# Logic.net
KiCad netlist of a schematic drawn in Altium Designer
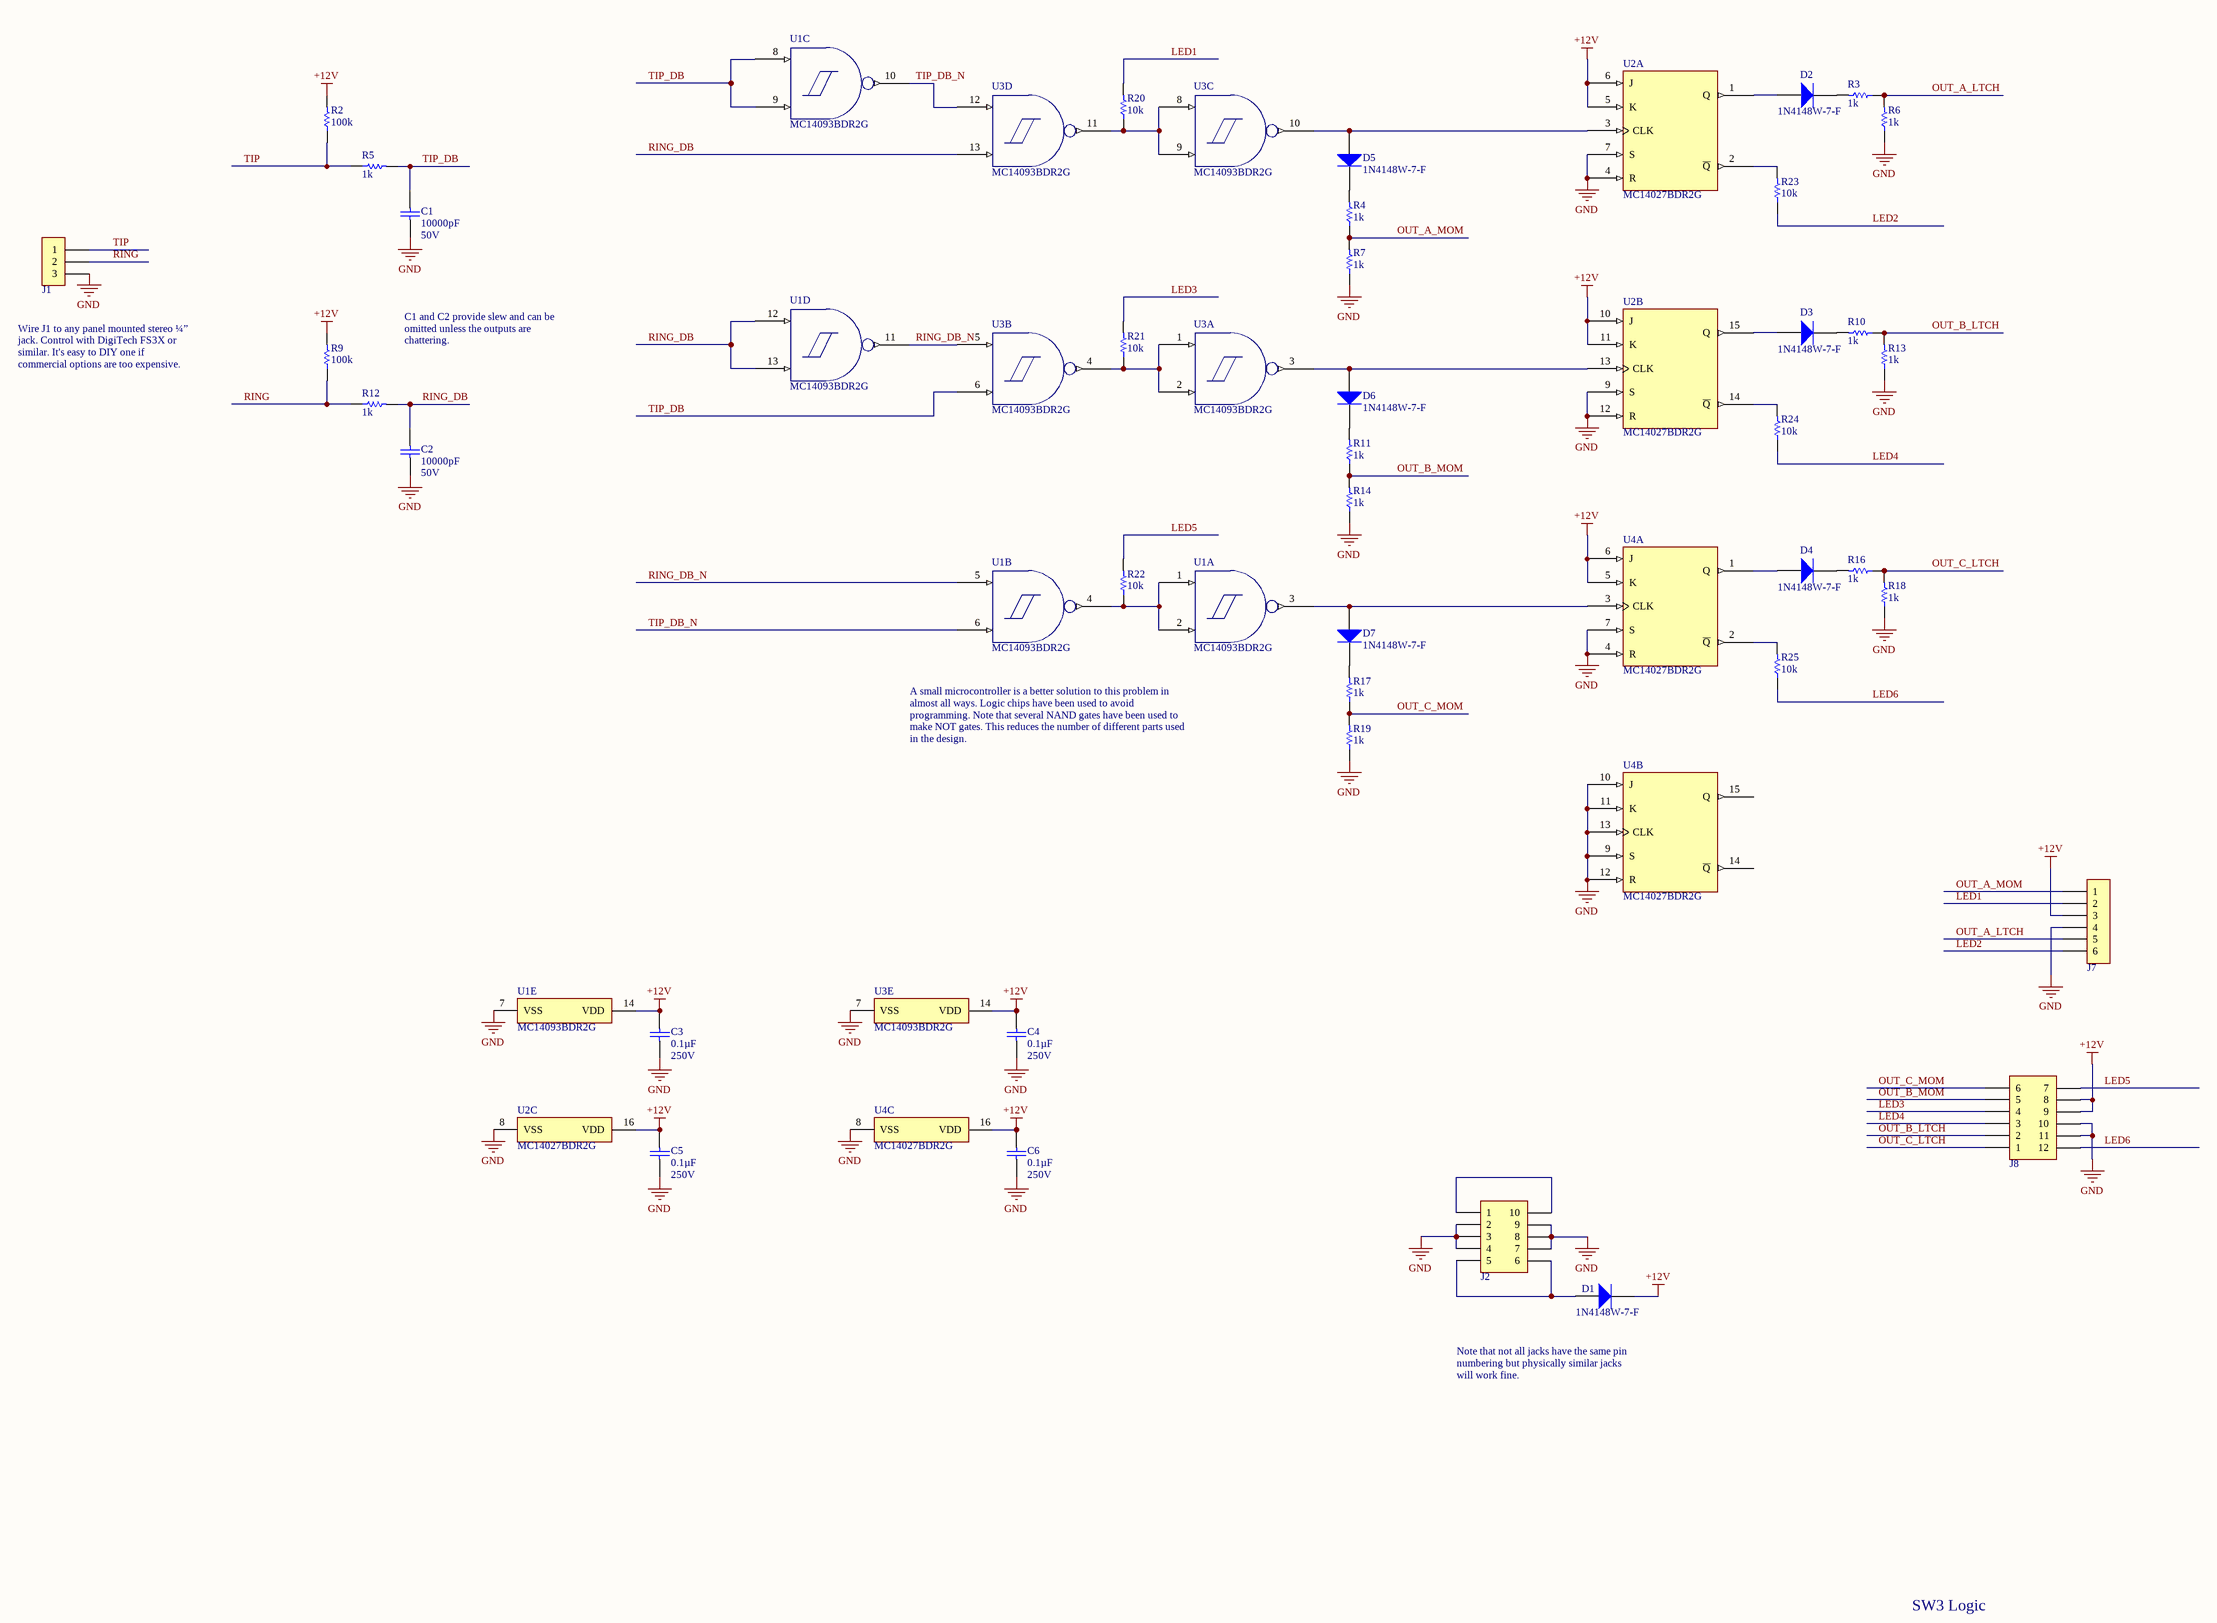
[diagram p0: Logic.SchDoc]

(export (version "E")
  (design (tool "Eeschema 10.0.6"))
  (components
    (comp (ref "C1")
      (value "10000pF")
      (footprint "Chip0805")
      (description "CAP CER 10000PF 50V 5% NP0 0805")
      (fields
        (field (name "VOLTAGE") "50V")
        (field (name "PARTNUMBER") "C2012C0G1H103J060AA")
        (field (name "MANUFACTURER") "TDK Corporation")
      )
      (libsource (lib "Passives") (part "CAP"))
    )
    (comp (ref "C2")
      (value "10000pF")
      (footprint "Chip0805")
      (description "CAP CER 10000PF 50V 5% NP0 0805")
      (fields
        (field (name "VOLTAGE") "50V")
        (field (name "PARTNUMBER") "C2012C0G1H103J060AA")
        (field (name "MANUFACTURER") "TDK Corporation")
      )
      (libsource (lib "Passives") (part "CAP"))
    )
    (comp (ref "C3")
      (value "0.1µF")
      (footprint "Chip0805")
      (description "CAP CER 0.1UF 250V 10% X7T 0805")
      (fields
        (field (name "VOLTAGE") "250V")
        (field (name "PARTNUMBER") "C2012X7T2E104K125AA")
        (field (name "MANUFACTURER") "TDK Corporation")
      )
      (libsource (lib "Passives") (part "CAP"))
    )
    (comp (ref "C4")
      (value "0.1µF")
      (footprint "Chip0805")
      (description "CAP CER 0.1UF 250V 10% X7T 0805")
      (fields
        (field (name "VOLTAGE") "250V")
        (field (name "PARTNUMBER") "C2012X7T2E104K125AA")
        (field (name "MANUFACTURER") "TDK Corporation")
      )
      (libsource (lib "Passives") (part "CAP"))
    )
    (comp (ref "C5")
      (value "0.1µF")
      (footprint "Chip0805")
      (description "CAP CER 0.1UF 250V 10% X7T 0805")
      (fields
        (field (name "VOLTAGE") "250V")
        (field (name "PARTNUMBER") "C2012X7T2E104K125AA")
        (field (name "MANUFACTURER") "TDK Corporation")
      )
      (libsource (lib "Passives") (part "CAP"))
    )
    (comp (ref "C6")
      (value "0.1µF")
      (footprint "Chip0805")
      (description "CAP CER 0.1UF 250V 10% X7T 0805")
      (fields
        (field (name "VOLTAGE") "250V")
        (field (name "PARTNUMBER") "C2012X7T2E104K125AA")
        (field (name "MANUFACTURER") "TDK Corporation")
      )
      (libsource (lib "Passives") (part "CAP"))
    )
    (comp (ref "D1")
      (value "1N4148W-7-F")
      (footprint "SOD-123")
      (description "DIODE SWITCH 100V 0.15A SOD123")
      (fields (field (name "MANUFACTURER") "Diodes Incorporated"))
      (libsource (lib "Semiconductor") (part "DIODE"))
    )
    (comp (ref "D2")
      (value "1N4148W-7-F")
      (footprint "SOD-123")
      (description "DIODE SWITCH 100V 0.15A SOD123")
      (fields (field (name "MANUFACTURER") "Diodes Incorporated"))
      (libsource (lib "Semiconductor") (part "DIODE"))
    )
    (comp (ref "D3")
      (value "1N4148W-7-F")
      (footprint "SOD-123")
      (description "DIODE SWITCH 100V 0.15A SOD123")
      (fields (field (name "MANUFACTURER") "Diodes Incorporated"))
      (libsource (lib "Semiconductor") (part "DIODE"))
    )
    (comp (ref "D4")
      (value "1N4148W-7-F")
      (footprint "SOD-123")
      (description "DIODE SWITCH 100V 0.15A SOD123")
      (fields (field (name "MANUFACTURER") "Diodes Incorporated"))
      (libsource (lib "Semiconductor") (part "DIODE"))
    )
    (comp (ref "D5")
      (value "1N4148W-7-F")
      (footprint "SOD-123")
      (description "DIODE SWITCH 100V 0.15A SOD123")
      (fields (field (name "MANUFACTURER") "Diodes Incorporated"))
      (libsource (lib "Semiconductor") (part "DIODE"))
    )
    (comp (ref "D6")
      (value "1N4148W-7-F")
      (footprint "SOD-123")
      (description "DIODE SWITCH 100V 0.15A SOD123")
      (fields (field (name "MANUFACTURER") "Diodes Incorporated"))
      (libsource (lib "Semiconductor") (part "DIODE"))
    )
    (comp (ref "D7")
      (value "1N4148W-7-F")
      (footprint "SOD-123")
      (description "DIODE SWITCH 100V 0.15A SOD123")
      (fields (field (name "MANUFACTURER") "Diodes Incorporated"))
      (libsource (lib "Semiconductor") (part "DIODE"))
    )
    (comp (ref "J1")
      (value "3-644456-3")
      (footprint "TE_3-644456-3")
      (description "CONN HEADER VERT 3POS .100 TIN")
      (fields (field (name "MANUFACTURER") "TE Connectivity"))
      (libsource (lib "Connectors") (part "HEADER_1x3"))
    )
    (comp (ref "J2")
      (value "75869-101LF")
      (footprint "IDC_100_2x5")
      (description "CONN HEADER 10POS DUAL VERT PCB")
      (fields (field (name "MANUFACTURER") "FCI"))
      (libsource (lib "Connectors") (part "HEADER_2x5"))
    )
    (comp (ref "J7")
      (value "535584-1")
      (footprint "TE_535584-1")
      (description "CONN RECEPT 6POS .100 VERT")
      (fields (field (name "MANUFACTURER") "TE Connectivity AMP Connectors"))
      (libsource (lib "Connectors") (part "HEADER_1x6"))
    )
    (comp (ref "J8")
      (value "5-534998-6")
      (footprint "TE_5-534998-6")
      (description "CONN RECEPT 12POS .100 VERT DUAL")
      (fields (field (name "MANUFACTURER") "TE Connectivity AMP Connectors"))
      (libsource (lib "Connectors") (part "HEADER_2x6"))
    )
    (comp (ref "R2")
      (value "100k")
      (footprint "Chip0805")
      (description "RES 100K OHM 1/8W 1% 0805 SMD")
      (fields (field (name "PARTNUMBER") "CRCW0805100KFKEA") (field (name "MANUFACTURER") "Vishay Dale"))
      (libsource (lib "Passives") (part "RES"))
    )
    (comp (ref "R3")
      (value "1k")
      (footprint "Chip0805")
      (description "RES 1.00K OHM 1/8W 1% 0805 SMD")
      (fields (field (name "PARTNUMBER") "CRCW08051K00FKEA") (field (name "MANUFACTURER") "Vishay Dale"))
      (libsource (lib "Passives") (part "RES"))
    )
    (comp (ref "R4")
      (value "1k")
      (footprint "Chip0805")
      (description "RES 1.00K OHM 1/8W 1% 0805 SMD")
      (fields (field (name "PARTNUMBER") "CRCW08051K00FKEA") (field (name "MANUFACTURER") "Vishay Dale"))
      (libsource (lib "Passives") (part "RES"))
    )
    (comp (ref "R5")
      (value "1k")
      (footprint "Chip0805")
      (description "RES 1.00K OHM 1/8W 1% 0805 SMD")
      (fields (field (name "PARTNUMBER") "CRCW08051K00FKEA") (field (name "MANUFACTURER") "Vishay Dale"))
      (libsource (lib "Passives") (part "RES"))
    )
    (comp (ref "R6")
      (value "1k")
      (footprint "Chip0805")
      (description "RES 1.00K OHM 1/8W 1% 0805 SMD")
      (fields (field (name "PARTNUMBER") "CRCW08051K00FKEA") (field (name "MANUFACTURER") "Vishay Dale"))
      (libsource (lib "Passives") (part "RES"))
    )
    (comp (ref "R7")
      (value "1k")
      (footprint "Chip0805")
      (description "RES 1.00K OHM 1/8W 1% 0805 SMD")
      (fields (field (name "PARTNUMBER") "CRCW08051K00FKEA") (field (name "MANUFACTURER") "Vishay Dale"))
      (libsource (lib "Passives") (part "RES"))
    )
    (comp (ref "R9")
      (value "100k")
      (footprint "Chip0805")
      (description "RES 100K OHM 1/8W 1% 0805 SMD")
      (fields (field (name "PARTNUMBER") "CRCW0805100KFKEA") (field (name "MANUFACTURER") "Vishay Dale"))
      (libsource (lib "Passives") (part "RES"))
    )
    (comp (ref "R10")
      (value "1k")
      (footprint "Chip0805")
      (description "RES 1.00K OHM 1/8W 1% 0805 SMD")
      (fields (field (name "PARTNUMBER") "CRCW08051K00FKEA") (field (name "MANUFACTURER") "Vishay Dale"))
      (libsource (lib "Passives") (part "RES"))
    )
    (comp (ref "R11")
      (value "1k")
      (footprint "Chip0805")
      (description "RES 1.00K OHM 1/8W 1% 0805 SMD")
      (fields (field (name "PARTNUMBER") "CRCW08051K00FKEA") (field (name "MANUFACTURER") "Vishay Dale"))
      (libsource (lib "Passives") (part "RES"))
    )
    (comp (ref "R12")
      (value "1k")
      (footprint "Chip0805")
      (description "RES 1.00K OHM 1/8W 1% 0805 SMD")
      (fields (field (name "PARTNUMBER") "CRCW08051K00FKEA") (field (name "MANUFACTURER") "Vishay Dale"))
      (libsource (lib "Passives") (part "RES"))
    )
    (comp (ref "R13")
      (value "1k")
      (footprint "Chip0805")
      (description "RES 1.00K OHM 1/8W 1% 0805 SMD")
      (fields (field (name "PARTNUMBER") "CRCW08051K00FKEA") (field (name "MANUFACTURER") "Vishay Dale"))
      (libsource (lib "Passives") (part "RES"))
    )
    (comp (ref "R14")
      (value "1k")
      (footprint "Chip0805")
      (description "RES 1.00K OHM 1/8W 1% 0805 SMD")
      (fields (field (name "PARTNUMBER") "CRCW08051K00FKEA") (field (name "MANUFACTURER") "Vishay Dale"))
      (libsource (lib "Passives") (part "RES"))
    )
    (comp (ref "R16")
      (value "1k")
      (footprint "Chip0805")
      (description "RES 1.00K OHM 1/8W 1% 0805 SMD")
      (fields (field (name "PARTNUMBER") "CRCW08051K00FKEA") (field (name "MANUFACTURER") "Vishay Dale"))
      (libsource (lib "Passives") (part "RES"))
    )
    (comp (ref "R17")
      (value "1k")
      (footprint "Chip0805")
      (description "RES 1.00K OHM 1/8W 1% 0805 SMD")
      (fields (field (name "PARTNUMBER") "CRCW08051K00FKEA") (field (name "MANUFACTURER") "Vishay Dale"))
      (libsource (lib "Passives") (part "RES"))
    )
    (comp (ref "R18")
      (value "1k")
      (footprint "Chip0805")
      (description "RES 1.00K OHM 1/8W 1% 0805 SMD")
      (fields (field (name "PARTNUMBER") "CRCW08051K00FKEA") (field (name "MANUFACTURER") "Vishay Dale"))
      (libsource (lib "Passives") (part "RES"))
    )
    (comp (ref "R19")
      (value "1k")
      (footprint "Chip0805")
      (description "RES 1.00K OHM 1/8W 1% 0805 SMD")
      (fields (field (name "PARTNUMBER") "CRCW08051K00FKEA") (field (name "MANUFACTURER") "Vishay Dale"))
      (libsource (lib "Passives") (part "RES"))
    )
    (comp (ref "R20")
      (value "10k")
      (footprint "Chip0805")
      (description "RES 10.0K OHM 1/8W 1% 0805 SMD")
      (fields (field (name "PARTNUMBER") "CRCW080510K0FKEA") (field (name "MANUFACTURER") "Vishay Dale"))
      (libsource (lib "Passives") (part "RES"))
    )
    (comp (ref "R21")
      (value "10k")
      (footprint "Chip0805")
      (description "RES 10.0K OHM 1/8W 1% 0805 SMD")
      (fields (field (name "PARTNUMBER") "CRCW080510K0FKEA") (field (name "MANUFACTURER") "Vishay Dale"))
      (libsource (lib "Passives") (part "RES"))
    )
    (comp (ref "R22")
      (value "10k")
      (footprint "Chip0805")
      (description "RES 10.0K OHM 1/8W 1% 0805 SMD")
      (fields (field (name "PARTNUMBER") "CRCW080510K0FKEA") (field (name "MANUFACTURER") "Vishay Dale"))
      (libsource (lib "Passives") (part "RES"))
    )
    (comp (ref "R23")
      (value "10k")
      (footprint "Chip0805")
      (description "RES 10.0K OHM 1/8W 1% 0805 SMD")
      (fields (field (name "PARTNUMBER") "CRCW080510K0FKEA") (field (name "MANUFACTURER") "Vishay Dale"))
      (libsource (lib "Passives") (part "RES"))
    )
    (comp (ref "R24")
      (value "10k")
      (footprint "Chip0805")
      (description "RES 10.0K OHM 1/8W 1% 0805 SMD")
      (fields (field (name "PARTNUMBER") "CRCW080510K0FKEA") (field (name "MANUFACTURER") "Vishay Dale"))
      (libsource (lib "Passives") (part "RES"))
    )
    (comp (ref "R25")
      (value "10k")
      (footprint "Chip0805")
      (description "RES 10.0K OHM 1/8W 1% 0805 SMD")
      (fields (field (name "PARTNUMBER") "CRCW080510K0FKEA") (field (name "MANUFACTURER") "Vishay Dale"))
      (libsource (lib "Passives") (part "RES"))
    )
    (comp (ref "U1")
      (value "MC14093BDR2G")
      (footprint "14-SOIC")
      (description "IC GATE NAND 4CH 2-INP 14SOIC")
      (fields (field (name "MANUFACTURER") "onsemi"))
      (libsource (lib "ICs") (part "Quad_Schmitt_NAND"))
    )
    (comp (ref "U2")
      (value "MC14027BDR2G")
      (footprint "16-SOIC")
      (description "IC FF JK TYPE DUAL 1BIT 16SOIC")
      (fields (field (name "MANUFACTURER") "onsemi"))
      (libsource (lib "ICs") (part "Dual_JK_FF"))
    )
    (comp (ref "U3")
      (value "MC14093BDR2G")
      (footprint "14-SOIC")
      (description "IC GATE NAND 4CH 2-INP 14SOIC")
      (fields (field (name "MANUFACTURER") "onsemi"))
      (libsource (lib "ICs") (part "Quad_Schmitt_NAND"))
    )
    (comp (ref "U4")
      (value "MC14027BDR2G")
      (footprint "16-SOIC")
      (description "IC FF JK TYPE DUAL 1BIT 16SOIC")
      (fields (field (name "MANUFACTURER") "onsemi"))
      (libsource (lib "ICs") (part "Dual_JK_FF"))
    )
  )
  (nets
    (net (code "1") (name "+12V") (class "Default")
      (node (ref "C3") (pin "2") (pinfunction "2_2") (pintype "passive"))
      (node (ref "C4") (pin "2") (pinfunction "2_2") (pintype "passive"))
      (node (ref "C5") (pin "2") (pinfunction "2_2") (pintype "passive"))
      (node (ref "C6") (pin "2") (pinfunction "2_2") (pintype "passive"))
      (node (ref "D1") (pin "1") (pinfunction "C_1") (pintype "passive"))
      (node (ref "J7") (pin "3") (pinfunction "3_3") (pintype "passive"))
      (node (ref "J8") (pin "8") (pinfunction "8_8") (pintype "passive"))
      (node (ref "J8") (pin "9") (pinfunction "9_9") (pintype "passive"))
      (node (ref "R2") (pin "2") (pinfunction "2_2") (pintype "passive"))
      (node (ref "R9") (pin "2") (pinfunction "2_2") (pintype "passive"))
      (node (ref "U1") (pin "14") (pinfunction "VDD_14") (pintype "passive"))
      (node (ref "U2") (pin "10") (pinfunction "J_10") (pintype "input"))
      (node (ref "U2") (pin "11") (pinfunction "K_11") (pintype "input"))
      (node (ref "U2") (pin "16") (pinfunction "VDD_16") (pintype "passive"))
      (node (ref "U2") (pin "5") (pinfunction "K_5") (pintype "input"))
      (node (ref "U2") (pin "6") (pinfunction "J_6") (pintype "input"))
      (node (ref "U3") (pin "14") (pinfunction "VDD_14") (pintype "passive"))
      (node (ref "U4") (pin "16") (pinfunction "VDD_16") (pintype "passive"))
      (node (ref "U4") (pin "5") (pinfunction "K_5") (pintype "input"))
      (node (ref "U4") (pin "6") (pinfunction "J_6") (pintype "input"))
    )
    (net (code "2") (name "/LED1") (class "Default")
      (node (ref "J7") (pin "2") (pinfunction "2_2") (pintype "passive"))
      (node (ref "R20") (pin "2") (pinfunction "2_2") (pintype "passive"))
    )
    (net (code "3") (name "/LED2") (class "Default")
      (node (ref "J7") (pin "6") (pinfunction "6_6") (pintype "passive"))
      (node (ref "R23") (pin "1") (pinfunction "1_1") (pintype "passive"))
    )
    (net (code "4") (name "/LED3") (class "Default")
      (node (ref "J8") (pin "4") (pinfunction "4_4") (pintype "passive"))
      (node (ref "R21") (pin "2") (pinfunction "2_2") (pintype "passive"))
    )
    (net (code "5") (name "/LED4") (class "Default")
      (node (ref "J8") (pin "3") (pinfunction "3_3") (pintype "passive"))
      (node (ref "R24") (pin "1") (pinfunction "1_1") (pintype "passive"))
    )
    (net (code "6") (name "/LED5") (class "Default")
      (node (ref "J8") (pin "7") (pinfunction "7_7") (pintype "passive"))
      (node (ref "R22") (pin "2") (pinfunction "2_2") (pintype "passive"))
    )
    (net (code "7") (name "/LED6") (class "Default")
      (node (ref "J8") (pin "12") (pinfunction "12_12") (pintype "passive"))
      (node (ref "R25") (pin "1") (pinfunction "1_1") (pintype "passive"))
    )
    (net (code "8") (name "/OUT_A_LTCH") (class "Default")
      (node (ref "J7") (pin "5") (pinfunction "5_5") (pintype "passive"))
      (node (ref "R3") (pin "1") (pinfunction "1_1") (pintype "passive"))
      (node (ref "R6") (pin "2") (pinfunction "2_2") (pintype "passive"))
    )
    (net (code "9") (name "/OUT_A_MOM") (class "Default")
      (node (ref "J7") (pin "1") (pinfunction "1_1") (pintype "passive"))
      (node (ref "R4") (pin "1") (pinfunction "1_1") (pintype "passive"))
      (node (ref "R7") (pin "2") (pinfunction "2_2") (pintype "passive"))
    )
    (net (code "10") (name "/OUT_B_LTCH") (class "Default")
      (node (ref "J8") (pin "2") (pinfunction "2_2") (pintype "passive"))
      (node (ref "R10") (pin "1") (pinfunction "1_1") (pintype "passive"))
      (node (ref "R13") (pin "2") (pinfunction "2_2") (pintype "passive"))
    )
    (net (code "11") (name "/OUT_B_MOM") (class "Default")
      (node (ref "J8") (pin "5") (pinfunction "5_5") (pintype "passive"))
      (node (ref "R11") (pin "1") (pinfunction "1_1") (pintype "passive"))
      (node (ref "R14") (pin "2") (pinfunction "2_2") (pintype "passive"))
    )
    (net (code "12") (name "/OUT_C_LTCH") (class "Default")
      (node (ref "J8") (pin "1") (pinfunction "1_1") (pintype "passive"))
      (node (ref "R16") (pin "1") (pinfunction "1_1") (pintype "passive"))
      (node (ref "R18") (pin "2") (pinfunction "2_2") (pintype "passive"))
    )
    (net (code "13") (name "/OUT_C_MOM") (class "Default")
      (node (ref "J8") (pin "6") (pinfunction "6_6") (pintype "passive"))
      (node (ref "R17") (pin "1") (pinfunction "1_1") (pintype "passive"))
      (node (ref "R19") (pin "2") (pinfunction "2_2") (pintype "passive"))
    )
    (net (code "14") (name "/RING") (class "Default")
      (node (ref "J1") (pin "2") (pinfunction "2_2") (pintype "passive"))
      (node (ref "R12") (pin "1") (pinfunction "1_1") (pintype "passive"))
      (node (ref "R9") (pin "1") (pinfunction "1_1") (pintype "passive"))
    )
    (net (code "15") (name "/RING_DB") (class "Default")
      (node (ref "C2") (pin "2") (pinfunction "2_2") (pintype "passive"))
      (node (ref "R12") (pin "2") (pinfunction "2_2") (pintype "passive"))
      (node (ref "U1") (pin "12") (pinfunction "12_12") (pintype "input"))
      (node (ref "U1") (pin "13") (pinfunction "13_13") (pintype "input"))
      (node (ref "U3") (pin "13") (pinfunction "13_13") (pintype "input"))
    )
    (net (code "16") (name "/RING_DB_N") (class "Default")
      (node (ref "U1") (pin "11") (pinfunction "11_11") (pintype "output"))
      (node (ref "U1") (pin "5") (pinfunction "5_5") (pintype "input"))
      (node (ref "U3") (pin "5") (pinfunction "5_5") (pintype "input"))
    )
    (net (code "17") (name "/TIP") (class "Default")
      (node (ref "J1") (pin "1") (pinfunction "1_1") (pintype "passive"))
      (node (ref "R2") (pin "1") (pinfunction "1_1") (pintype "passive"))
      (node (ref "R5") (pin "1") (pinfunction "1_1") (pintype "passive"))
    )
    (net (code "18") (name "/TIP_DB") (class "Default")
      (node (ref "C1") (pin "2") (pinfunction "2_2") (pintype "passive"))
      (node (ref "R5") (pin "2") (pinfunction "2_2") (pintype "passive"))
      (node (ref "U1") (pin "8") (pinfunction "8_8") (pintype "input"))
      (node (ref "U1") (pin "9") (pinfunction "9_9") (pintype "input"))
      (node (ref "U3") (pin "6") (pinfunction "6_6") (pintype "input"))
    )
    (net (code "19") (name "/TIP_DB_N") (class "Default")
      (node (ref "U1") (pin "10") (pinfunction "10_10") (pintype "output"))
      (node (ref "U1") (pin "6") (pinfunction "6_6") (pintype "input"))
      (node (ref "U3") (pin "12") (pinfunction "12_12") (pintype "input"))
    )
    (net (code "20") (name "GND") (class "Default")
      (node (ref "C1") (pin "1") (pinfunction "1_1") (pintype "passive"))
      (node (ref "C2") (pin "1") (pinfunction "1_1") (pintype "passive"))
      (node (ref "C3") (pin "1") (pinfunction "1_1") (pintype "passive"))
      (node (ref "C4") (pin "1") (pinfunction "1_1") (pintype "passive"))
      (node (ref "C5") (pin "1") (pinfunction "1_1") (pintype "passive"))
      (node (ref "C6") (pin "1") (pinfunction "1_1") (pintype "passive"))
      (node (ref "J1") (pin "3") (pinfunction "3_3") (pintype "passive"))
      (node (ref "J2") (pin "2") (pinfunction "2_2") (pintype "passive"))
      (node (ref "J2") (pin "3") (pinfunction "3_3") (pintype "passive"))
      (node (ref "J2") (pin "4") (pinfunction "4_4") (pintype "passive"))
      (node (ref "J2") (pin "7") (pinfunction "7_7") (pintype "passive"))
      (node (ref "J2") (pin "8") (pinfunction "8_8") (pintype "passive"))
      (node (ref "J2") (pin "9") (pinfunction "9_9") (pintype "passive"))
      (node (ref "J7") (pin "4") (pinfunction "4_4") (pintype "passive"))
      (node (ref "J8") (pin "10") (pinfunction "10_10") (pintype "passive"))
      (node (ref "J8") (pin "11") (pinfunction "11_11") (pintype "passive"))
      (node (ref "R13") (pin "1") (pinfunction "1_1") (pintype "passive"))
      (node (ref "R14") (pin "1") (pinfunction "1_1") (pintype "passive"))
      (node (ref "R18") (pin "1") (pinfunction "1_1") (pintype "passive"))
      (node (ref "R19") (pin "1") (pinfunction "1_1") (pintype "passive"))
      (node (ref "R6") (pin "1") (pinfunction "1_1") (pintype "passive"))
      (node (ref "R7") (pin "1") (pinfunction "1_1") (pintype "passive"))
      (node (ref "U1") (pin "7") (pinfunction "VSS_7") (pintype "passive"))
      (node (ref "U2") (pin "12") (pinfunction "R_12") (pintype "input"))
      (node (ref "U2") (pin "4") (pinfunction "R_4") (pintype "input"))
      (node (ref "U2") (pin "7") (pinfunction "S_7") (pintype "input"))
      (node (ref "U2") (pin "8") (pinfunction "VSS_8") (pintype "passive"))
      (node (ref "U2") (pin "9") (pinfunction "S_9") (pintype "input"))
      (node (ref "U3") (pin "7") (pinfunction "VSS_7") (pintype "passive"))
      (node (ref "U4") (pin "10") (pinfunction "J_10") (pintype "input"))
      (node (ref "U4") (pin "11") (pinfunction "K_11") (pintype "input"))
      (node (ref "U4") (pin "12") (pinfunction "R_12") (pintype "input"))
      (node (ref "U4") (pin "13") (pinfunction "CLK_13") (pintype "input"))
      (node (ref "U4") (pin "4") (pinfunction "R_4") (pintype "input"))
      (node (ref "U4") (pin "7") (pinfunction "S_7") (pintype "input"))
      (node (ref "U4") (pin "8") (pinfunction "VSS_8") (pintype "passive"))
      (node (ref "U4") (pin "9") (pinfunction "S_9") (pintype "input"))
    )
    (net (code "21") (name "Net-(D1-A)") (class "Default")
      (node (ref "D1") (pin "2") (pinfunction "A_2") (pintype "passive"))
      (node (ref "J2") (pin "5") (pinfunction "5_5") (pintype "passive"))
      (node (ref "J2") (pin "6") (pinfunction "6_6") (pintype "passive"))
    )
    (net (code "22") (name "Net-(D2-A)") (class "Default")
      (node (ref "D2") (pin "2") (pinfunction "A_2") (pintype "passive"))
      (node (ref "U2") (pin "1") (pinfunction "Q_1") (pintype "output"))
    )
    (net (code "23") (name "Net-(D2-C)") (class "Default")
      (node (ref "D2") (pin "1") (pinfunction "C_1") (pintype "passive"))
      (node (ref "R3") (pin "2") (pinfunction "2_2") (pintype "passive"))
    )
    (net (code "24") (name "Net-(D3-A)") (class "Default")
      (node (ref "D3") (pin "2") (pinfunction "A_2") (pintype "passive"))
      (node (ref "U2") (pin "15") (pinfunction "Q_15") (pintype "output"))
    )
    (net (code "25") (name "Net-(D3-C)") (class "Default")
      (node (ref "D3") (pin "1") (pinfunction "C_1") (pintype "passive"))
      (node (ref "R10") (pin "2") (pinfunction "2_2") (pintype "passive"))
    )
    (net (code "26") (name "Net-(D4-A)") (class "Default")
      (node (ref "D4") (pin "2") (pinfunction "A_2") (pintype "passive"))
      (node (ref "U4") (pin "1") (pinfunction "Q_1") (pintype "output"))
    )
    (net (code "27") (name "Net-(D4-C)") (class "Default")
      (node (ref "D4") (pin "1") (pinfunction "C_1") (pintype "passive"))
      (node (ref "R16") (pin "2") (pinfunction "2_2") (pintype "passive"))
    )
    (net (code "28") (name "Net-(D5-A)") (class "Default")
      (node (ref "D5") (pin "2") (pinfunction "A_2") (pintype "passive"))
      (node (ref "U2") (pin "3") (pinfunction "CLK_3") (pintype "input"))
      (node (ref "U3") (pin "10") (pinfunction "10_10") (pintype "output"))
    )
    (net (code "29") (name "Net-(D5-C)") (class "Default")
      (node (ref "D5") (pin "1") (pinfunction "C_1") (pintype "passive"))
      (node (ref "R4") (pin "2") (pinfunction "2_2") (pintype "passive"))
    )
    (net (code "30") (name "Net-(D6-A)") (class "Default")
      (node (ref "D6") (pin "2") (pinfunction "A_2") (pintype "passive"))
      (node (ref "U2") (pin "13") (pinfunction "CLK_13") (pintype "input"))
      (node (ref "U3") (pin "3") (pinfunction "3_3") (pintype "output"))
    )
    (net (code "31") (name "Net-(D6-C)") (class "Default")
      (node (ref "D6") (pin "1") (pinfunction "C_1") (pintype "passive"))
      (node (ref "R11") (pin "2") (pinfunction "2_2") (pintype "passive"))
    )
    (net (code "32") (name "Net-(D7-A)") (class "Default")
      (node (ref "D7") (pin "2") (pinfunction "A_2") (pintype "passive"))
      (node (ref "U1") (pin "3") (pinfunction "3_3") (pintype "output"))
      (node (ref "U4") (pin "3") (pinfunction "CLK_3") (pintype "input"))
    )
    (net (code "33") (name "Net-(D7-C)") (class "Default")
      (node (ref "D7") (pin "1") (pinfunction "C_1") (pintype "passive"))
      (node (ref "R17") (pin "2") (pinfunction "2_2") (pintype "passive"))
    )
    (net (code "34") (name "Net-(J2-Pad1)") (class "Default")
      (node (ref "J2") (pin "1") (pinfunction "1_1") (pintype "passive"))
      (node (ref "J2") (pin "10") (pinfunction "10_10") (pintype "passive"))
    )
    (net (code "35") (name "Net-(R20-Pad1)") (class "Default")
      (node (ref "R20") (pin "1") (pinfunction "1_1") (pintype "passive"))
      (node (ref "U3") (pin "11") (pinfunction "11_11") (pintype "output"))
      (node (ref "U3") (pin "8") (pinfunction "8_8") (pintype "input"))
      (node (ref "U3") (pin "9") (pinfunction "9_9") (pintype "input"))
    )
    (net (code "36") (name "Net-(R21-Pad1)") (class "Default")
      (node (ref "R21") (pin "1") (pinfunction "1_1") (pintype "passive"))
      (node (ref "U3") (pin "1") (pinfunction "1_1") (pintype "input"))
      (node (ref "U3") (pin "2") (pinfunction "2_2") (pintype "input"))
      (node (ref "U3") (pin "4") (pinfunction "4_4") (pintype "output"))
    )
    (net (code "37") (name "Net-(R22-Pad1)") (class "Default")
      (node (ref "R22") (pin "1") (pinfunction "1_1") (pintype "passive"))
      (node (ref "U1") (pin "1") (pinfunction "1_1") (pintype "input"))
      (node (ref "U1") (pin "2") (pinfunction "2_2") (pintype "input"))
      (node (ref "U1") (pin "4") (pinfunction "4_4") (pintype "output"))
    )
    (net (code "38") (name "Net-(U2A-~{Q})") (class "Default")
      (node (ref "R23") (pin "2") (pinfunction "2_2") (pintype "passive"))
      (node (ref "U2") (pin "2") (pinfunction "~{Q}_2") (pintype "output"))
    )
    (net (code "39") (name "Net-(U2B-~{Q})") (class "Default")
      (node (ref "R24") (pin "2") (pinfunction "2_2") (pintype "passive"))
      (node (ref "U2") (pin "14") (pinfunction "~{Q}_14") (pintype "output"))
    )
    (net (code "40") (name "Net-(U4A-~{Q})") (class "Default")
      (node (ref "R25") (pin "2") (pinfunction "2_2") (pintype "passive"))
      (node (ref "U4") (pin "2") (pinfunction "~{Q}_2") (pintype "output"))
    )
    (net (code "41") (name "unconnected-(U4B-Q-Pad15)") (class "Default")
      (node (ref "U4") (pin "15") (pinfunction "Q_15") (pintype "output"))
    )
    (net (code "42") (name "unconnected-(U4B-~{Q}-Pad14)") (class "Default")
      (node (ref "U4") (pin "14") (pinfunction "~{Q}_14") (pintype "output"))
    )
  )
)
